# cpu-OLED-rtm.net
KiCad netlist of a schematic drawn in EAGLE
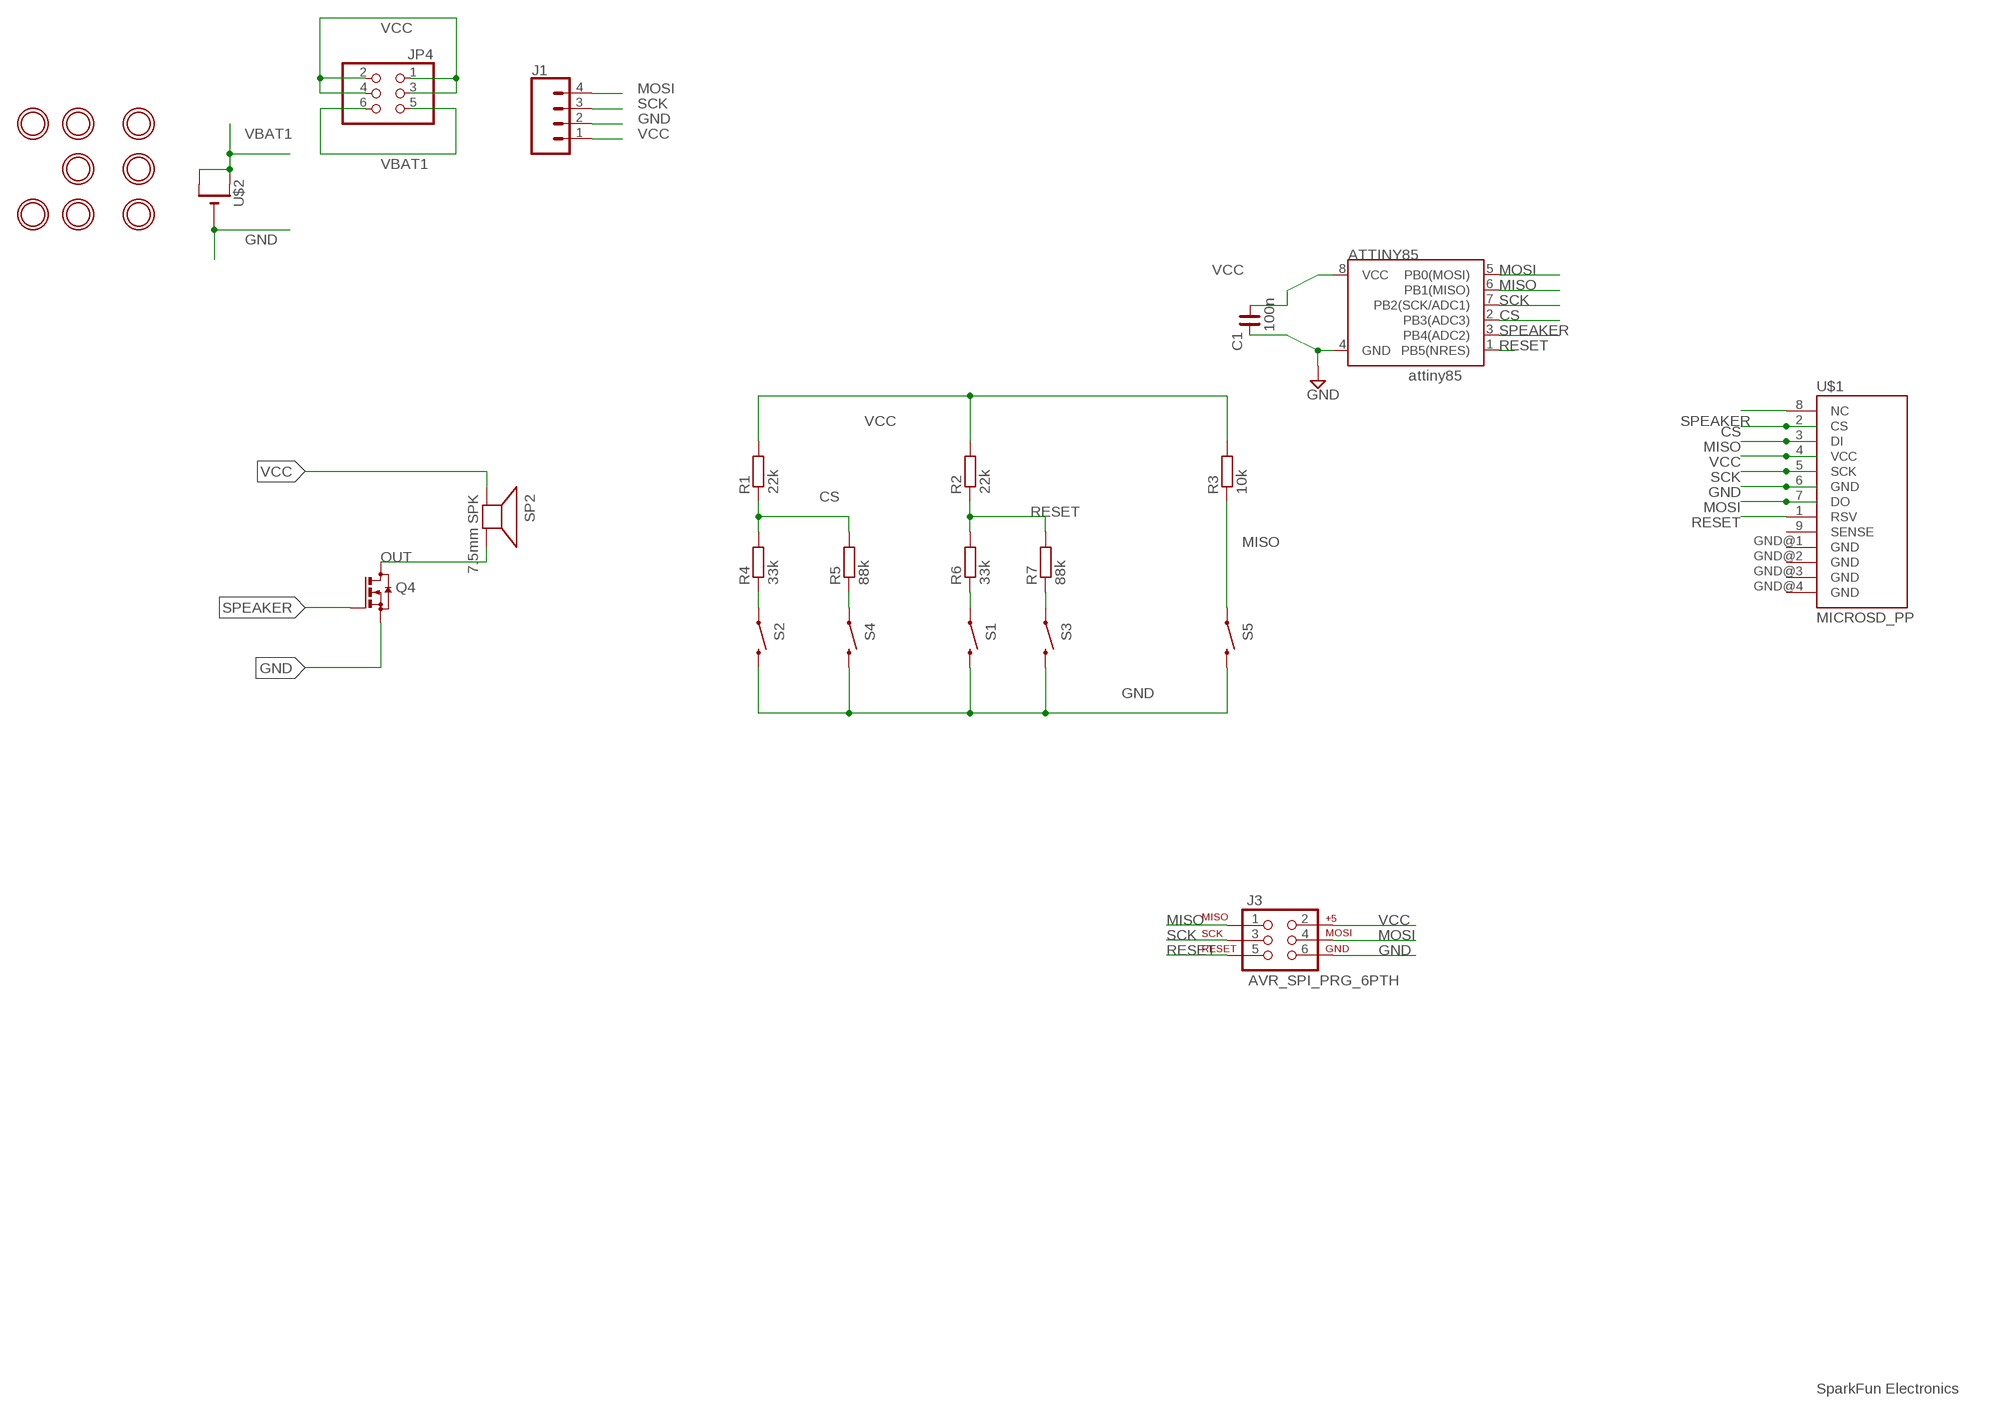
[diagram p0: schematic, sheet 1]

(export (version "E")
  (design (tool "Eeschema 10.0.6"))
  (components
    (comp (ref "ATTINY85")
      (value "ATTINY45")
      (footprint "eagle-import:SO08-EIAJ")
      (libsource (lib "eagle-import") (part "ATTINY45"))
    )
    (comp (ref "C1")
      (value "100n")
      (footprint "eagle-import:C0805")
      (libsource (lib "eagle-import") (part "C_0805"))
    )
    (comp (ref "J1")
      (value "CONN_041X04_NO_SILK")
      (footprint "eagle-import:1X04_NO_SILK")
      (libsource (lib "eagle-import") (part "CONN_041X04_NO_SILK"))
    )
    (comp (ref "J3")
      (value "AVR_SPI_PRG_6PTH")
      (footprint "eagle-import:2X3")
      (libsource (lib "eagle-import") (part "AVR_SPI_PRG_6PTH"))
    )
    (comp (ref "JP4")
      (value "PINHD-2X3")
      (footprint "eagle-import:2X03")
      (libsource (lib "eagle-import") (part "PINHD-2X3"))
    )
    (comp (ref "Q4")
      (value "BSS123")
      (footprint "eagle-import:SOT23")
      (libsource (lib "eagle-import") (part "BSS123"))
    )
    (comp (ref "R1")
      (value "22k")
      (footprint "eagle-import:R0805")
      (libsource (lib "eagle-import") (part "R-EU_R0805"))
    )
    (comp (ref "R2")
      (value "22k")
      (footprint "eagle-import:R0805")
      (libsource (lib "eagle-import") (part "R-EU_R0805"))
    )
    (comp (ref "R3")
      (value "10k")
      (footprint "eagle-import:R0805")
      (libsource (lib "eagle-import") (part "R-EU_R0805"))
    )
    (comp (ref "R4")
      (value "33k")
      (footprint "eagle-import:R0805")
      (libsource (lib "eagle-import") (part "R-EU_R0805"))
    )
    (comp (ref "R5")
      (value "88k")
      (footprint "eagle-import:R0805")
      (libsource (lib "eagle-import") (part "R-EU_R0805"))
    )
    (comp (ref "R6")
      (value "33k")
      (footprint "eagle-import:R0805")
      (libsource (lib "eagle-import") (part "R-EU_R0805"))
    )
    (comp (ref "R7")
      (value "88k")
      (footprint "eagle-import:R0805")
      (libsource (lib "eagle-import") (part "R-EU_R0805"))
    )
    (comp (ref "S1")
      (value "SWITCH-MOMENTARY-2SMD-4")
      (footprint "eagle-import:TACTILE_SWITCH_TALL")
      (libsource (lib "eagle-import") (part "SWITCH-MOMENTARY-2SMD-4"))
    )
    (comp (ref "S2")
      (value "SWITCH-MOMENTARY-2SMD-4")
      (footprint "eagle-import:TACTILE_SWITCH_TALL")
      (libsource (lib "eagle-import") (part "SWITCH-MOMENTARY-2SMD-4"))
    )
    (comp (ref "S3")
      (value "SWITCH-MOMENTARY-2SMD-4")
      (footprint "eagle-import:TACTILE_SWITCH_TALL")
      (libsource (lib "eagle-import") (part "SWITCH-MOMENTARY-2SMD-4"))
    )
    (comp (ref "S4")
      (value "SWITCH-MOMENTARY-2SMD-4")
      (footprint "eagle-import:TACTILE_SWITCH_TALL")
      (libsource (lib "eagle-import") (part "SWITCH-MOMENTARY-2SMD-4"))
    )
    (comp (ref "S5")
      (value "SWITCH-MOMENTARY-2SMD-4")
      (footprint "eagle-import:TACTILE_SWITCH_TALL")
      (libsource (lib "eagle-import") (part "SWITCH-MOMENTARY-2SMD-4"))
    )
    (comp (ref "SP2")
      (value "7.5mm SPK")
      (footprint "eagle-import:BUZZER_SMT_5MM")
      (libsource (lib "eagle-import") (part "SPEAKER_BUZZER5MM"))
    )
    (comp (ref "U$1")
      (value "MICROSD_PP")
      (footprint "eagle-import:MICROSD_PP")
      (libsource (lib "eagle-import") (part "MICROSD_PP"))
    )
    (comp (ref "U$2")
      (value "CR2032THM")
      (footprint "eagle-import:CR2032-THRU")
      (libsource (lib "eagle-import") (part "CR2032THM"))
    )
    (comp (ref "U$3")
      (value "MOUNTINGHOLE2.0")
      (footprint "eagle-import:MOUNTINGHOLE_2.0_PLATED")
      (libsource (lib "eagle-import") (part "MOUNTINGHOLE2.0"))
    )
    (comp (ref "U$4")
      (value "MOUNTINGHOLE2.0")
      (footprint "eagle-import:MOUNTINGHOLE_2.0_PLATED")
      (libsource (lib "eagle-import") (part "MOUNTINGHOLE2.0"))
    )
    (comp (ref "U$5")
      (value "MOUNTINGHOLE2.0")
      (footprint "eagle-import:MOUNTINGHOLE_2.0_PLATED")
      (libsource (lib "eagle-import") (part "MOUNTINGHOLE2.0"))
    )
    (comp (ref "U$6")
      (value "MOUNTINGHOLE2.0")
      (footprint "eagle-import:MOUNTINGHOLE_2.0_PLATED")
      (libsource (lib "eagle-import") (part "MOUNTINGHOLE2.0"))
    )
    (comp (ref "U$7")
      (value "MOUNTINGHOLE2.0")
      (footprint "eagle-import:MOUNTINGHOLE_2.0_PLATED")
      (libsource (lib "eagle-import") (part "MOUNTINGHOLE2.0"))
    )
    (comp (ref "U$8")
      (value "MOUNTINGHOLE2.0")
      (footprint "eagle-import:MOUNTINGHOLE_2.0_PLATED")
      (libsource (lib "eagle-import") (part "MOUNTINGHOLE2.0"))
    )
    (comp (ref "U$9")
      (value "MOUNTINGHOLE2.0")
      (footprint "eagle-import:MOUNTINGHOLE_2.0_PLATED")
      (libsource (lib "eagle-import") (part "MOUNTINGHOLE2.0"))
    )
    (comp (ref "U$11")
      (value "MOUNTINGHOLE2.0")
      (footprint "eagle-import:MOUNTINGHOLE_2.0_PLATED")
      (libsource (lib "eagle-import") (part "MOUNTINGHOLE2.0"))
    )
  )
  (nets
    (net (code "1") (name "/CS") (class "Default")
      (node (ref "ATTINY85") (pin "2") (pinfunction "PB3(ADC3)_2") (pintype "bidirectional"))
      (node (ref "R1") (pin "1") (pinfunction "1_1") (pintype "passive"))
      (node (ref "R4") (pin "2") (pinfunction "2_2") (pintype "passive"))
      (node (ref "R5") (pin "2") (pinfunction "2_2") (pintype "passive"))
      (node (ref "U$1") (pin "2") (pinfunction "CS_2") (pintype "bidirectional"))
    )
    (net (code "2") (name "/MISO") (class "Default")
      (node (ref "ATTINY85") (pin "6") (pinfunction "PB1(MISO)_6") (pintype "bidirectional"))
      (node (ref "J3") (pin "1") (pinfunction "1_1") (pintype "passive"))
      (node (ref "R3") (pin "1") (pinfunction "1_1") (pintype "passive"))
      (node (ref "S5") (pin "A2") (pinfunction "1_A2") (pintype "passive"))
      (node (ref "U$1") (pin "3") (pinfunction "DI_3") (pintype "bidirectional"))
    )
    (net (code "3") (name "/MOSI") (class "Default")
      (node (ref "ATTINY85") (pin "5") (pinfunction "PB0(MOSI)_5") (pintype "bidirectional"))
      (node (ref "J1") (pin "4") (pinfunction "4_4") (pintype "passive"))
      (node (ref "J3") (pin "4") (pinfunction "4_4") (pintype "passive"))
      (node (ref "U$1") (pin "7") (pinfunction "DO_7") (pintype "bidirectional"))
    )
    (net (code "4") (name "/OUT") (class "Default")
      (node (ref "Q4") (pin "3") (pinfunction "D_3") (pintype "passive"))
      (node (ref "SP2") (pin "-") (pinfunction "-_-") (pintype "passive"))
    )
    (net (code "5") (name "/RESET") (class "Default")
      (node (ref "ATTINY85") (pin "1") (pinfunction "PB5(NRES)_1") (pintype "bidirectional"))
      (node (ref "J3") (pin "5") (pinfunction "5_5") (pintype "passive"))
      (node (ref "R2") (pin "1") (pinfunction "1_1") (pintype "passive"))
      (node (ref "R6") (pin "2") (pinfunction "2_2") (pintype "passive"))
      (node (ref "R7") (pin "2") (pinfunction "2_2") (pintype "passive"))
      (node (ref "U$1") (pin "1") (pinfunction "RSV_1") (pintype "bidirectional"))
    )
    (net (code "6") (name "/SCK") (class "Default")
      (node (ref "ATTINY85") (pin "7") (pinfunction "PB2(SCK/ADC1)_7") (pintype "bidirectional"))
      (node (ref "J1") (pin "3") (pinfunction "3_3") (pintype "passive"))
      (node (ref "J3") (pin "3") (pinfunction "3_3") (pintype "passive"))
      (node (ref "U$1") (pin "5") (pinfunction "SCK_5") (pintype "bidirectional"))
    )
    (net (code "7") (name "/VBAT1") (class "Default")
      (node (ref "JP4") (pin "5") (pinfunction "5_5") (pintype "passive"))
      (node (ref "JP4") (pin "6") (pinfunction "6_6") (pintype "passive"))
      (node (ref "U$2") (pin "+1") (pinfunction "+_+1") (pintype "passive"))
      (node (ref "U$2") (pin "+2") (pinfunction "+1_+2") (pintype "passive"))
    )
    (net (code "8") (name "GND") (class "Default")
      (node (ref "ATTINY85") (pin "4") (pinfunction "GND_4") (pintype "bidirectional"))
      (node (ref "C1") (pin "2") (pinfunction "2_2") (pintype "passive"))
      (node (ref "J1") (pin "2") (pinfunction "2_2") (pintype "passive"))
      (node (ref "J3") (pin "6") (pinfunction "6_6") (pintype "passive"))
      (node (ref "Q4") (pin "2") (pinfunction "S_2") (pintype "passive"))
      (node (ref "S1") (pin "B2") (pinfunction "2_B2") (pintype "passive"))
      (node (ref "S2") (pin "B2") (pinfunction "2_B2") (pintype "passive"))
      (node (ref "S3") (pin "B2") (pinfunction "2_B2") (pintype "passive"))
      (node (ref "S4") (pin "B2") (pinfunction "2_B2") (pintype "passive"))
      (node (ref "S5") (pin "B2") (pinfunction "2_B2") (pintype "passive"))
      (node (ref "U$1") (pin "6") (pinfunction "GND_6") (pintype "bidirectional"))
      (node (ref "U$2") (pin "-") (pinfunction "-_-") (pintype "passive"))
    )
    (net (code "9") (name "Net-(S1-1)") (class "Default")
      (node (ref "R6") (pin "1") (pinfunction "1_1") (pintype "passive"))
      (node (ref "S1") (pin "A2") (pinfunction "1_A2") (pintype "passive"))
    )
    (net (code "10") (name "Net-(S2-1)") (class "Default")
      (node (ref "R4") (pin "1") (pinfunction "1_1") (pintype "passive"))
      (node (ref "S2") (pin "A2") (pinfunction "1_A2") (pintype "passive"))
    )
    (net (code "11") (name "Net-(S3-1)") (class "Default")
      (node (ref "R7") (pin "1") (pinfunction "1_1") (pintype "passive"))
      (node (ref "S3") (pin "A2") (pinfunction "1_A2") (pintype "passive"))
    )
    (net (code "12") (name "Net-(S4-1)") (class "Default")
      (node (ref "R5") (pin "1") (pinfunction "1_1") (pintype "passive"))
      (node (ref "S4") (pin "A2") (pinfunction "1_A2") (pintype "passive"))
    )
    (net (code "13") (name "SPEAKER") (class "Default")
      (node (ref "ATTINY85") (pin "3") (pinfunction "PB4(ADC2)_3") (pintype "bidirectional"))
      (node (ref "Q4") (pin "1") (pinfunction "G_1") (pintype "passive"))
      (node (ref "U$1") (pin "8") (pinfunction "NC_8") (pintype "bidirectional"))
    )
    (net (code "14") (name "VCC") (class "Default")
      (node (ref "ATTINY85") (pin "8") (pinfunction "VCC_8") (pintype "bidirectional"))
      (node (ref "C1") (pin "1") (pinfunction "1_1") (pintype "passive"))
      (node (ref "J1") (pin "1") (pinfunction "1_1") (pintype "passive"))
      (node (ref "J3") (pin "2") (pinfunction "2_2") (pintype "passive"))
      (node (ref "JP4") (pin "1") (pinfunction "1_1") (pintype "passive"))
      (node (ref "JP4") (pin "2") (pinfunction "2_2") (pintype "passive"))
      (node (ref "JP4") (pin "3") (pinfunction "3_3") (pintype "passive"))
      (node (ref "JP4") (pin "4") (pinfunction "4_4") (pintype "passive"))
      (node (ref "R1") (pin "2") (pinfunction "2_2") (pintype "passive"))
      (node (ref "R2") (pin "2") (pinfunction "2_2") (pintype "passive"))
      (node (ref "R3") (pin "2") (pinfunction "2_2") (pintype "passive"))
      (node (ref "SP2") (pin "+") (pinfunction "+_+") (pintype "passive"))
      (node (ref "U$1") (pin "4") (pinfunction "VCC_4") (pintype "bidirectional"))
    )
    (net (code "15") (name "unconnected-(U$1-GND-PadGND@1)") (class "Default")
      (node (ref "U$1") (pin "GND@1") (pinfunction "GND_GND@1") (pintype "bidirectional"))
    )
    (net (code "16") (name "unconnected-(U$1-GND-PadGND@2)") (class "Default")
      (node (ref "U$1") (pin "GND@2") (pinfunction "GND_GND@2") (pintype "bidirectional"))
    )
    (net (code "17") (name "unconnected-(U$1-GND-PadGND@3)") (class "Default")
      (node (ref "U$1") (pin "GND@3") (pinfunction "GND_GND@3") (pintype "bidirectional"))
    )
    (net (code "18") (name "unconnected-(U$1-GND-PadGND@4)") (class "Default")
      (node (ref "U$1") (pin "GND@4") (pinfunction "GND_GND@4") (pintype "bidirectional"))
    )
    (net (code "19") (name "unconnected-(U$1-SENSE-Pad9)") (class "Default")
      (node (ref "U$1") (pin "9") (pinfunction "SENSE_9") (pintype "bidirectional"))
    )
  )
)
